# Driver.net
KiCad netlist of a schematic drawn in EAGLE
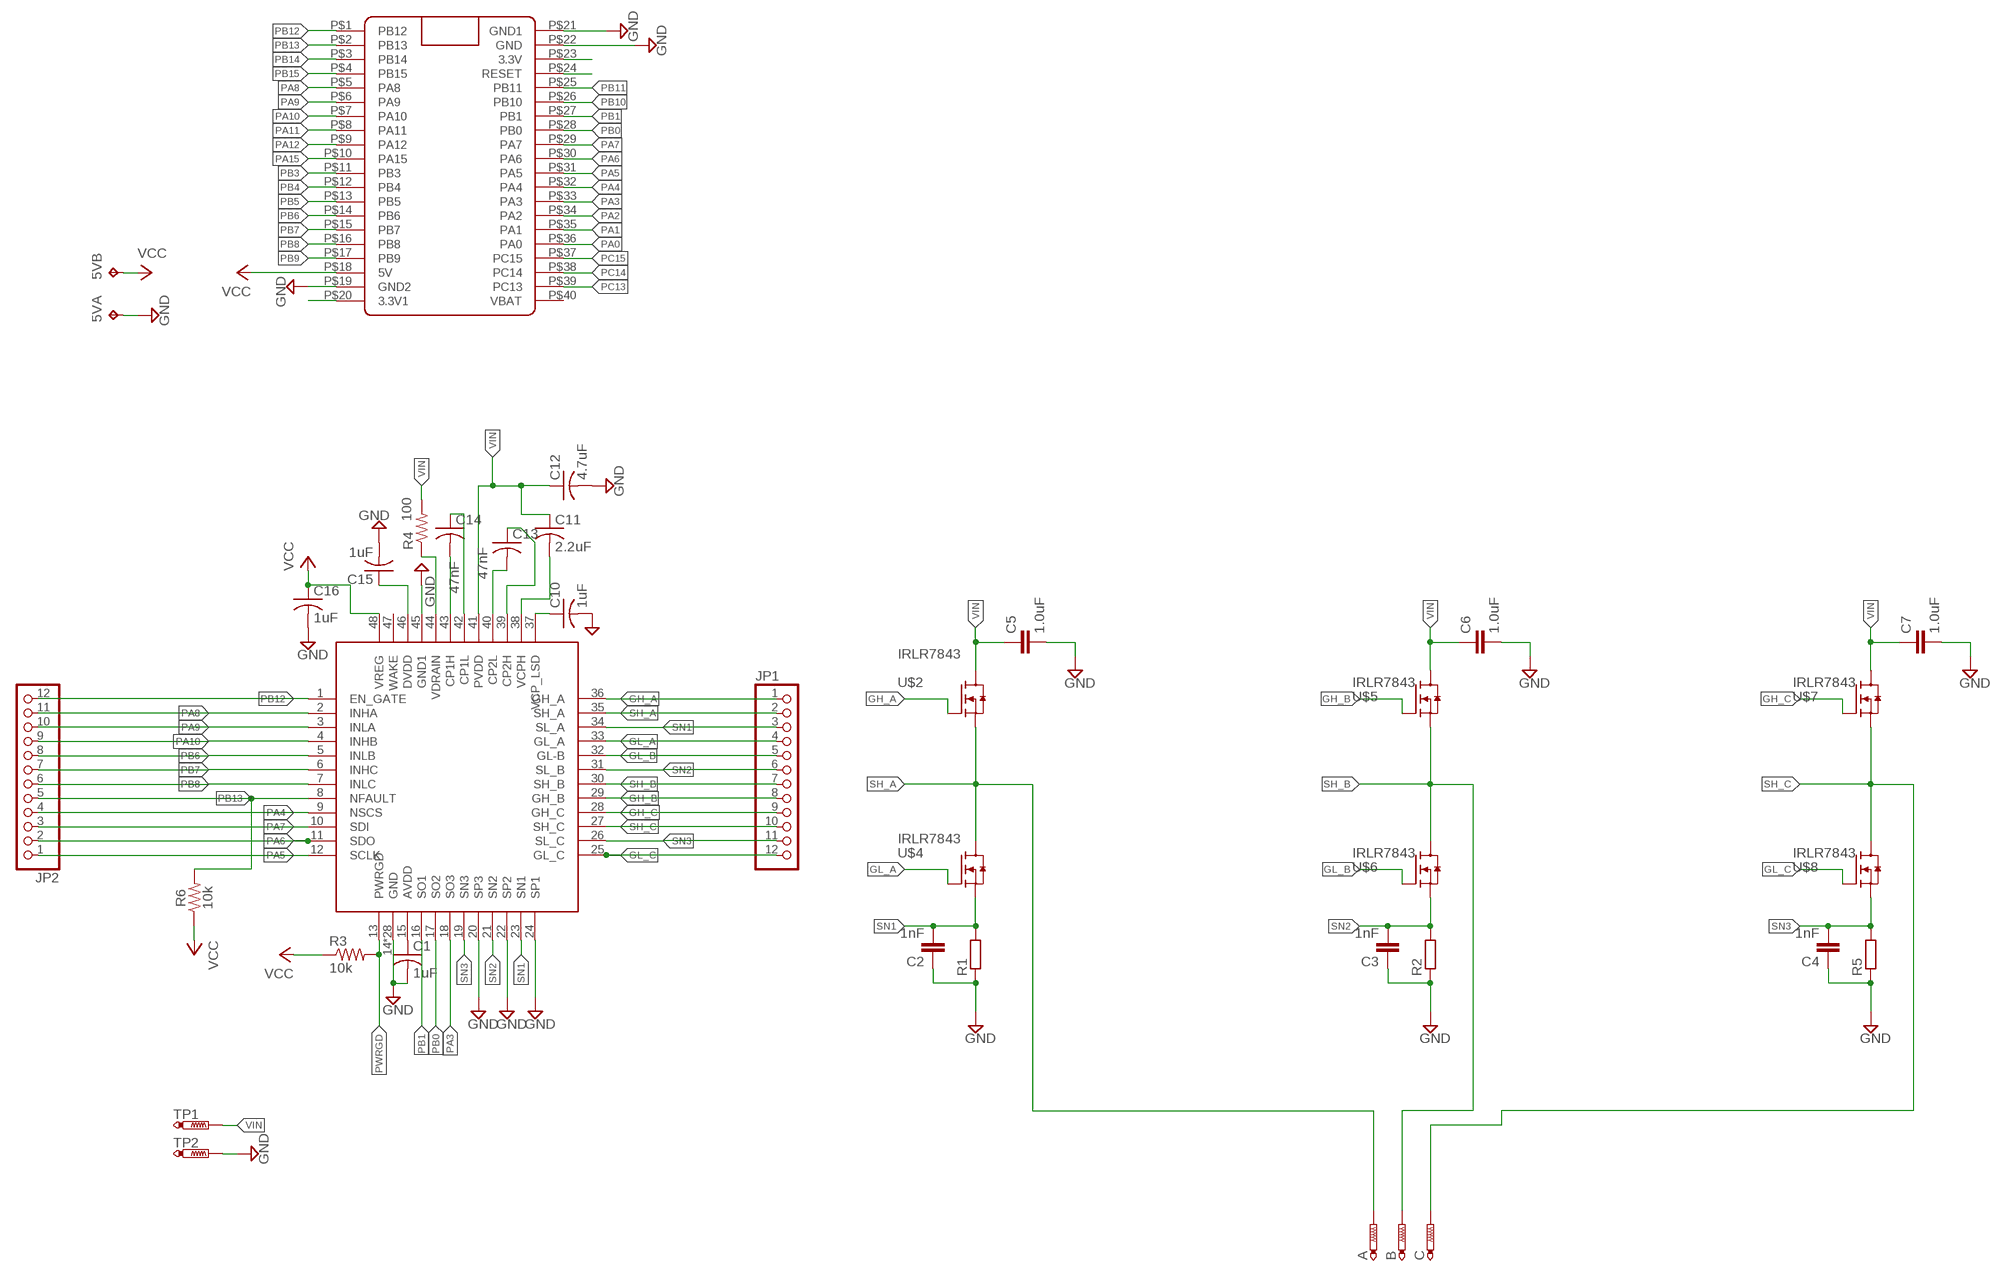
[diagram p0: schematic, sheet 1]

(export (version "E")
  (design (tool "Eeschema 10.0.6"))
  (components
    (comp (ref "5V")
      (value "TP2P2-38-17")
      (footprint "eagle-import:P2-38-17")
      (libsource (lib "eagle-import") (part "TP2P2-38-17"))
    )
    (comp (ref "A")
      (value "PTR1PAD1-20Y")
      (footprint "eagle-import:P1-20Y")
      (libsource (lib "eagle-import") (part "PTR1PAD1-20Y"))
    )
    (comp (ref "B")
      (value "PTR1PAD1-20Y")
      (footprint "eagle-import:P1-20Y")
      (libsource (lib "eagle-import") (part "PTR1PAD1-20Y"))
    )
    (comp (ref "C")
      (value "PTR1PAD1-20Y")
      (footprint "eagle-import:P1-20Y")
      (libsource (lib "eagle-import") (part "PTR1PAD1-20Y"))
    )
    (comp (ref "C1")
      (value "1uF")
      (footprint "eagle-import:C0603")
      (libsource (lib "eagle-import") (part "C-USC0603"))
    )
    (comp (ref "C2")
      (value "1nF")
      (footprint "eagle-import:0603")
      (libsource (lib "eagle-import") (part "1.0NF/1000PF-0603-50V-10%"))
    )
    (comp (ref "C3")
      (value "1nF")
      (footprint "eagle-import:0603")
      (libsource (lib "eagle-import") (part "1.0NF/1000PF-0603-50V-10%"))
    )
    (comp (ref "C4")
      (value "1nF")
      (footprint "eagle-import:0603")
      (libsource (lib "eagle-import") (part "1.0NF/1000PF-0603-50V-10%"))
    )
    (comp (ref "C5")
      (value "1.0uF")
      (footprint "eagle-import:0603")
      (libsource (lib "eagle-import") (part "1.0UF-0603-16V-10%-X7R"))
    )
    (comp (ref "C6")
      (value "1.0uF")
      (footprint "eagle-import:0603")
      (libsource (lib "eagle-import") (part "1.0UF-0603-16V-10%-X7R"))
    )
    (comp (ref "C7")
      (value "1.0uF")
      (footprint "eagle-import:0603")
      (libsource (lib "eagle-import") (part "1.0UF-0603-16V-10%-X7R"))
    )
    (comp (ref "C10")
      (value "1uF")
      (footprint "eagle-import:C0603")
      (libsource (lib "eagle-import") (part "C-USC0603"))
    )
    (comp (ref "C11")
      (value "2.2uF")
      (footprint "eagle-import:C0603")
      (libsource (lib "eagle-import") (part "C-USC0603"))
    )
    (comp (ref "C12")
      (value "4.7uF")
      (footprint "eagle-import:C0603")
      (libsource (lib "eagle-import") (part "C-USC0603"))
    )
    (comp (ref "C13")
      (value "47nF")
      (footprint "eagle-import:C0603")
      (libsource (lib "eagle-import") (part "C-USC0603"))
    )
    (comp (ref "C14")
      (value "47nF")
      (footprint "eagle-import:C0603")
      (libsource (lib "eagle-import") (part "C-USC0603"))
    )
    (comp (ref "C15")
      (value "1uF")
      (footprint "eagle-import:C0603")
      (libsource (lib "eagle-import") (part "C-USC0603"))
    )
    (comp (ref "C16")
      (value "1uF")
      (footprint "eagle-import:C0603")
      (libsource (lib "eagle-import") (part "C-USC0603"))
    )
    (comp (ref "JP1")
      (value "PINHD-1X12")
      (footprint "eagle-import:1X12")
      (libsource (lib "eagle-import") (part "PINHD-1X12"))
    )
    (comp (ref "JP2")
      (value "PINHD-1X12")
      (footprint "eagle-import:1X12")
      (libsource (lib "eagle-import") (part "PINHD-1X12"))
    )
    (comp (ref "R1")
      (value "R-EU_R2512")
      (footprint "eagle-import:R2512")
      (libsource (lib "eagle-import") (part "R-EU_R2512"))
    )
    (comp (ref "R2")
      (value "R-EU_R2512")
      (footprint "eagle-import:R2512")
      (libsource (lib "eagle-import") (part "R-EU_R2512"))
    )
    (comp (ref "R3")
      (value "10k")
      (footprint "eagle-import:R0603")
      (libsource (lib "eagle-import") (part "R-US_R0603"))
    )
    (comp (ref "R4")
      (value "100")
      (footprint "eagle-import:R0603")
      (libsource (lib "eagle-import") (part "R-US_R0603"))
    )
    (comp (ref "R5")
      (value "R-EU_R2512")
      (footprint "eagle-import:R2512")
      (libsource (lib "eagle-import") (part "R-EU_R2512"))
    )
    (comp (ref "R6")
      (value "10k")
      (footprint "eagle-import:0603")
      (libsource (lib "eagle-import") (part "10KOHM-0603-1/10W-1%"))
    )
    (comp (ref "TP1")
      (value "PTR1PAD1-20Y")
      (footprint "eagle-import:P1-20Y")
      (libsource (lib "eagle-import") (part "PTR1PAD1-20Y"))
    )
    (comp (ref "TP2")
      (value "PTR1PAD1-20Y")
      (footprint "eagle-import:P1-20Y")
      (libsource (lib "eagle-import") (part "PTR1PAD1-20Y"))
    )
    (comp (ref "U$1")
      (value "BLUE_PILLADVANCED")
      (footprint "eagle-import:BLUE_PILL_ADV")
      (libsource (lib "eagle-import") (part "BLUE_PILLADVANCED"))
    )
    (comp (ref "U$2")
      (value "IRLR7843")
      (footprint "eagle-import:TO252")
      (libsource (lib "eagle-import") (part "IRLR7843"))
    )
    (comp (ref "U$3")
      (value "DRV8305")
      (footprint "eagle-import:PFB_S-PQFP-G48")
      (libsource (lib "eagle-import") (part "DRV8305"))
    )
    (comp (ref "U$4")
      (value "IRLR7843")
      (footprint "eagle-import:TO252")
      (libsource (lib "eagle-import") (part "IRLR7843"))
    )
    (comp (ref "U$5")
      (value "IRLR7843")
      (footprint "eagle-import:TO252")
      (libsource (lib "eagle-import") (part "IRLR7843"))
    )
    (comp (ref "U$6")
      (value "IRLR7843")
      (footprint "eagle-import:TO252")
      (libsource (lib "eagle-import") (part "IRLR7843"))
    )
    (comp (ref "U$7")
      (value "IRLR7843")
      (footprint "eagle-import:TO252")
      (libsource (lib "eagle-import") (part "IRLR7843"))
    )
    (comp (ref "U$8")
      (value "IRLR7843")
      (footprint "eagle-import:TO252")
      (libsource (lib "eagle-import") (part "IRLR7843"))
    )
  )
  (nets
    (net (code "1") (name "GH_A") (class "Default")
      (node (ref "JP1") (pin "1") (pinfunction "1_1") (pintype "passive"))
      (node (ref "U$2") (pin "1") (pinfunction "G_1") (pintype "passive"))
      (node (ref "U$3") (pin "36") (pinfunction "GH_A_36") (pintype "bidirectional"))
    )
    (net (code "2") (name "GH_B") (class "Default")
      (node (ref "JP1") (pin "8") (pinfunction "8_8") (pintype "passive"))
      (node (ref "U$3") (pin "29") (pinfunction "GH_B_29") (pintype "bidirectional"))
      (node (ref "U$5") (pin "1") (pinfunction "G_1") (pintype "passive"))
    )
    (net (code "3") (name "GH_C") (class "Default")
      (node (ref "JP1") (pin "9") (pinfunction "9_9") (pintype "passive"))
      (node (ref "U$3") (pin "28") (pinfunction "GH_C_28") (pintype "bidirectional"))
      (node (ref "U$7") (pin "1") (pinfunction "G_1") (pintype "passive"))
    )
    (net (code "4") (name "GL_A") (class "Default")
      (node (ref "JP1") (pin "4") (pinfunction "4_4") (pintype "passive"))
      (node (ref "U$3") (pin "33") (pinfunction "GL_A_33") (pintype "bidirectional"))
      (node (ref "U$4") (pin "1") (pinfunction "G_1") (pintype "passive"))
    )
    (net (code "5") (name "GL_B") (class "Default")
      (node (ref "JP1") (pin "5") (pinfunction "5_5") (pintype "passive"))
      (node (ref "U$3") (pin "32") (pinfunction "GL-B_32") (pintype "bidirectional"))
      (node (ref "U$6") (pin "1") (pinfunction "G_1") (pintype "passive"))
    )
    (net (code "6") (name "GL_C") (class "Default")
      (node (ref "JP1") (pin "12") (pinfunction "12_12") (pintype "passive"))
      (node (ref "U$3") (pin "25") (pinfunction "GL_C_25") (pintype "bidirectional"))
      (node (ref "U$8") (pin "1") (pinfunction "G_1") (pintype "passive"))
    )
    (net (code "7") (name "GND") (class "Default")
      (node (ref "5V") (pin "TP-1") (pinfunction "TP_TP-1") (pintype "input"))
      (node (ref "C1") (pin "2") (pinfunction "2_2") (pintype "passive"))
      (node (ref "C10") (pin "2") (pinfunction "2_2") (pintype "passive"))
      (node (ref "C12") (pin "2") (pinfunction "2_2") (pintype "passive"))
      (node (ref "C15") (pin "2") (pinfunction "2_2") (pintype "passive"))
      (node (ref "C16") (pin "2") (pinfunction "2_2") (pintype "passive"))
      (node (ref "C2") (pin "1") (pinfunction "1_1") (pintype "passive"))
      (node (ref "C3") (pin "1") (pinfunction "1_1") (pintype "passive"))
      (node (ref "C4") (pin "1") (pinfunction "1_1") (pintype "passive"))
      (node (ref "C5") (pin "2") (pinfunction "2_2") (pintype "passive"))
      (node (ref "C6") (pin "2") (pinfunction "2_2") (pintype "passive"))
      (node (ref "C7") (pin "2") (pinfunction "2_2") (pintype "passive"))
      (node (ref "R1") (pin "1") (pinfunction "1_1") (pintype "passive"))
      (node (ref "R2") (pin "1") (pinfunction "1_1") (pintype "passive"))
      (node (ref "R5") (pin "1") (pinfunction "1_1") (pintype "passive"))
      (node (ref "TP2") (pin "TP") (pinfunction "TP_TP") (pintype "input"))
      (node (ref "U$1") (pin "P$19") (pinfunction "GND2_P$19") (pintype "bidirectional"))
      (node (ref "U$1") (pin "P$21") (pinfunction "GND1_P$21") (pintype "power_in"))
      (node (ref "U$1") (pin "P$22") (pinfunction "GND_P$22") (pintype "bidirectional"))
      (node (ref "U$3") (pin "14") (pinfunction "GND_14") (pintype "bidirectional"))
      (node (ref "U$3") (pin "20") (pinfunction "SP3_20") (pintype "bidirectional"))
      (node (ref "U$3") (pin "22") (pinfunction "SP2_22") (pintype "bidirectional"))
      (node (ref "U$3") (pin "24") (pinfunction "SP1_24") (pintype "bidirectional"))
      (node (ref "U$3") (pin "45") (pinfunction "GND1_45") (pintype "bidirectional"))
      (node (ref "U$3") (pin "P$1") (pinfunction "GND_P$1") (pintype "bidirectional"))
      (node (ref "U$3") (pin "P$10") (pinfunction "GND_P$10") (pintype "bidirectional"))
      (node (ref "U$3") (pin "P$11") (pinfunction "GND_P$11") (pintype "bidirectional"))
      (node (ref "U$3") (pin "P$12") (pinfunction "GND_P$12") (pintype "bidirectional"))
      (node (ref "U$3") (pin "P$13") (pinfunction "GND_P$13") (pintype "bidirectional"))
      (node (ref "U$3") (pin "P$14") (pinfunction "GND_P$14") (pintype "bidirectional"))
      (node (ref "U$3") (pin "P$15") (pinfunction "GND_P$15") (pintype "bidirectional"))
      (node (ref "U$3") (pin "P$16") (pinfunction "GND_P$16") (pintype "bidirectional"))
      (node (ref "U$3") (pin "P$17") (pinfunction "GND_P$17") (pintype "bidirectional"))
      (node (ref "U$3") (pin "P$18") (pinfunction "GND_P$18") (pintype "bidirectional"))
      (node (ref "U$3") (pin "P$19") (pinfunction "GND_P$19") (pintype "bidirectional"))
      (node (ref "U$3") (pin "P$2") (pinfunction "GND_P$2") (pintype "bidirectional"))
      (node (ref "U$3") (pin "P$20") (pinfunction "GND_P$20") (pintype "bidirectional"))
      (node (ref "U$3") (pin "P$21") (pinfunction "GND_P$21") (pintype "bidirectional"))
      (node (ref "U$3") (pin "P$22") (pinfunction "GND_P$22") (pintype "bidirectional"))
      (node (ref "U$3") (pin "P$23") (pinfunction "GND_P$23") (pintype "bidirectional"))
      (node (ref "U$3") (pin "P$24") (pinfunction "GND_P$24") (pintype "bidirectional"))
      (node (ref "U$3") (pin "P$25") (pinfunction "GND_P$25") (pintype "bidirectional"))
      (node (ref "U$3") (pin "P$26") (pinfunction "GND_P$26") (pintype "bidirectional"))
      (node (ref "U$3") (pin "P$27") (pinfunction "GND_P$27") (pintype "bidirectional"))
      (node (ref "U$3") (pin "P$3") (pinfunction "GND_P$3") (pintype "bidirectional"))
      (node (ref "U$3") (pin "P$4") (pinfunction "GND_P$4") (pintype "bidirectional"))
      (node (ref "U$3") (pin "P$5") (pinfunction "GND_P$5") (pintype "bidirectional"))
      (node (ref "U$3") (pin "P$6") (pinfunction "GND_P$6") (pintype "bidirectional"))
      (node (ref "U$3") (pin "P$7") (pinfunction "GND_P$7") (pintype "bidirectional"))
      (node (ref "U$3") (pin "P$8") (pinfunction "GND_P$8") (pintype "bidirectional"))
      (node (ref "U$3") (pin "P$9") (pinfunction "GND_P$9") (pintype "bidirectional"))
    )
    (net (code "8") (name "Net-(U$3-AVDD)") (class "Default")
      (node (ref "C1") (pin "1") (pinfunction "1_1") (pintype "passive"))
      (node (ref "U$3") (pin "15") (pinfunction "AVDD_15") (pintype "bidirectional"))
    )
    (net (code "9") (name "Net-(U$3-CP1H)") (class "Default")
      (node (ref "C14") (pin "2") (pinfunction "2_2") (pintype "passive"))
      (node (ref "U$3") (pin "43") (pinfunction "CP1H_43") (pintype "bidirectional"))
    )
    (net (code "10") (name "Net-(U$3-CP1L)") (class "Default")
      (node (ref "C14") (pin "1") (pinfunction "1_1") (pintype "passive"))
      (node (ref "U$3") (pin "42") (pinfunction "CP1L_42") (pintype "bidirectional"))
    )
    (net (code "11") (name "Net-(U$3-CP2H)") (class "Default")
      (node (ref "C13") (pin "1") (pinfunction "1_1") (pintype "passive"))
      (node (ref "U$3") (pin "39") (pinfunction "CP2H_39") (pintype "bidirectional"))
    )
    (net (code "12") (name "Net-(U$3-CP2L)") (class "Default")
      (node (ref "C13") (pin "2") (pinfunction "2_2") (pintype "passive"))
      (node (ref "U$3") (pin "40") (pinfunction "CP2L_40") (pintype "bidirectional"))
    )
    (net (code "13") (name "Net-(U$3-DVDD)") (class "Default")
      (node (ref "C15") (pin "1") (pinfunction "1_1") (pintype "passive"))
      (node (ref "U$3") (pin "46") (pinfunction "DVDD_46") (pintype "bidirectional"))
    )
    (net (code "14") (name "Net-(U$3-VCPH)") (class "Default")
      (node (ref "C11") (pin "2") (pinfunction "2_2") (pintype "passive"))
      (node (ref "U$3") (pin "38") (pinfunction "VCPH_38") (pintype "bidirectional"))
    )
    (net (code "15") (name "Net-(U$3-VCP_LSD)") (class "Default")
      (node (ref "C10") (pin "1") (pinfunction "1_1") (pintype "passive"))
      (node (ref "U$3") (pin "37") (pinfunction "VCP_LSD_37") (pintype "bidirectional"))
    )
    (net (code "16") (name "Net-(U$3-VDRAIN)") (class "Default")
      (node (ref "R4") (pin "1") (pinfunction "1_1") (pintype "passive"))
      (node (ref "U$3") (pin "44") (pinfunction "VDRAIN_44") (pintype "bidirectional"))
    )
    (net (code "17") (name "PA0") (class "Default")
      (node (ref "U$1") (pin "P$36") (pinfunction "PA0_P$36") (pintype "bidirectional"))
    )
    (net (code "18") (name "PA1") (class "Default")
      (node (ref "U$1") (pin "P$35") (pinfunction "PA1_P$35") (pintype "bidirectional"))
    )
    (net (code "19") (name "PA2") (class "Default")
      (node (ref "U$1") (pin "P$34") (pinfunction "PA2_P$34") (pintype "bidirectional"))
    )
    (net (code "20") (name "PA3") (class "Default")
      (node (ref "U$1") (pin "P$33") (pinfunction "PA3_P$33") (pintype "bidirectional"))
      (node (ref "U$3") (pin "18") (pinfunction "SO3_18") (pintype "bidirectional"))
    )
    (net (code "21") (name "PA4") (class "Default")
      (node (ref "JP2") (pin "4") (pinfunction "4_4") (pintype "passive"))
      (node (ref "U$1") (pin "P$32") (pinfunction "PA4_P$32") (pintype "bidirectional"))
      (node (ref "U$3") (pin "9") (pinfunction "NSCS_9") (pintype "bidirectional"))
    )
    (net (code "22") (name "PA5") (class "Default")
      (node (ref "JP2") (pin "1") (pinfunction "1_1") (pintype "passive"))
      (node (ref "U$1") (pin "P$31") (pinfunction "PA5_P$31") (pintype "bidirectional"))
      (node (ref "U$3") (pin "12") (pinfunction "SCLK_12") (pintype "bidirectional"))
    )
    (net (code "23") (name "PA6") (class "Default")
      (node (ref "JP2") (pin "2") (pinfunction "2_2") (pintype "passive"))
      (node (ref "U$1") (pin "P$30") (pinfunction "PA6_P$30") (pintype "bidirectional"))
      (node (ref "U$3") (pin "11") (pinfunction "SDO_11") (pintype "bidirectional"))
    )
    (net (code "24") (name "PA7") (class "Default")
      (node (ref "JP2") (pin "3") (pinfunction "3_3") (pintype "passive"))
      (node (ref "U$1") (pin "P$29") (pinfunction "PA7_P$29") (pintype "bidirectional"))
      (node (ref "U$3") (pin "10") (pinfunction "SDI_10") (pintype "bidirectional"))
    )
    (net (code "25") (name "PA8") (class "Default")
      (node (ref "JP2") (pin "11") (pinfunction "11_11") (pintype "passive"))
      (node (ref "U$1") (pin "P$5") (pinfunction "PA8_P$5") (pintype "bidirectional"))
      (node (ref "U$3") (pin "2") (pinfunction "INHA_2") (pintype "bidirectional"))
    )
    (net (code "26") (name "PA9") (class "Default")
      (node (ref "JP2") (pin "10") (pinfunction "10_10") (pintype "passive"))
      (node (ref "U$1") (pin "P$6") (pinfunction "PA9_P$6") (pintype "bidirectional"))
      (node (ref "U$3") (pin "3") (pinfunction "INLA_3") (pintype "bidirectional"))
    )
    (net (code "27") (name "PA10") (class "Default")
      (node (ref "JP2") (pin "9") (pinfunction "9_9") (pintype "passive"))
      (node (ref "U$1") (pin "P$7") (pinfunction "PA10_P$7") (pintype "bidirectional"))
      (node (ref "U$3") (pin "4") (pinfunction "INHB_4") (pintype "bidirectional"))
    )
    (net (code "28") (name "PA11") (class "Default")
      (node (ref "U$1") (pin "P$8") (pinfunction "PA11_P$8") (pintype "bidirectional"))
    )
    (net (code "29") (name "PA12") (class "Default")
      (node (ref "U$1") (pin "P$9") (pinfunction "PA12_P$9") (pintype "bidirectional"))
    )
    (net (code "30") (name "PA15") (class "Default")
      (node (ref "U$1") (pin "P$10") (pinfunction "PA15_P$10") (pintype "bidirectional"))
    )
    (net (code "31") (name "PB0") (class "Default")
      (node (ref "U$1") (pin "P$28") (pinfunction "PB0_P$28") (pintype "bidirectional"))
      (node (ref "U$3") (pin "17") (pinfunction "SO2_17") (pintype "bidirectional"))
    )
    (net (code "32") (name "PB1") (class "Default")
      (node (ref "U$1") (pin "P$27") (pinfunction "PB1_P$27") (pintype "bidirectional"))
      (node (ref "U$3") (pin "16") (pinfunction "SO1_16") (pintype "bidirectional"))
    )
    (net (code "33") (name "PB3") (class "Default")
      (node (ref "U$1") (pin "P$11") (pinfunction "PB3_P$11") (pintype "bidirectional"))
    )
    (net (code "34") (name "PB4") (class "Default")
      (node (ref "U$1") (pin "P$12") (pinfunction "PB4_P$12") (pintype "bidirectional"))
    )
    (net (code "35") (name "PB5") (class "Default")
      (node (ref "U$1") (pin "P$13") (pinfunction "PB5_P$13") (pintype "bidirectional"))
    )
    (net (code "36") (name "PB6") (class "Default")
      (node (ref "JP2") (pin "8") (pinfunction "8_8") (pintype "passive"))
      (node (ref "U$1") (pin "P$14") (pinfunction "PB6_P$14") (pintype "bidirectional"))
      (node (ref "U$3") (pin "5") (pinfunction "INLB_5") (pintype "bidirectional"))
    )
    (net (code "37") (name "PB7") (class "Default")
      (node (ref "JP2") (pin "7") (pinfunction "7_7") (pintype "passive"))
      (node (ref "U$1") (pin "P$15") (pinfunction "PB7_P$15") (pintype "bidirectional"))
      (node (ref "U$3") (pin "6") (pinfunction "INHC_6") (pintype "bidirectional"))
    )
    (net (code "38") (name "PB8") (class "Default")
      (node (ref "JP2") (pin "6") (pinfunction "6_6") (pintype "passive"))
      (node (ref "U$1") (pin "P$16") (pinfunction "PB8_P$16") (pintype "bidirectional"))
      (node (ref "U$3") (pin "7") (pinfunction "INLC_7") (pintype "bidirectional"))
    )
    (net (code "39") (name "PB9") (class "Default")
      (node (ref "U$1") (pin "P$17") (pinfunction "PB9_P$17") (pintype "bidirectional"))
    )
    (net (code "40") (name "PB10") (class "Default")
      (node (ref "U$1") (pin "P$26") (pinfunction "PB10_P$26") (pintype "bidirectional"))
    )
    (net (code "41") (name "PB11") (class "Default")
      (node (ref "U$1") (pin "P$25") (pinfunction "PB11_P$25") (pintype "bidirectional"))
    )
    (net (code "42") (name "PB12") (class "Default")
      (node (ref "JP2") (pin "12") (pinfunction "12_12") (pintype "passive"))
      (node (ref "U$1") (pin "P$1") (pinfunction "PB12_P$1") (pintype "bidirectional"))
      (node (ref "U$3") (pin "1") (pinfunction "EN_GATE_1") (pintype "bidirectional"))
    )
    (net (code "43") (name "PB13") (class "Default")
      (node (ref "JP2") (pin "5") (pinfunction "5_5") (pintype "passive"))
      (node (ref "R6") (pin "2") (pinfunction "2_2") (pintype "passive"))
      (node (ref "U$1") (pin "P$2") (pinfunction "PB13_P$2") (pintype "bidirectional"))
      (node (ref "U$3") (pin "8") (pinfunction "NFAULT_8") (pintype "bidirectional"))
    )
    (net (code "44") (name "PB14") (class "Default")
      (node (ref "U$1") (pin "P$3") (pinfunction "PB14_P$3") (pintype "bidirectional"))
    )
    (net (code "45") (name "PB15") (class "Default")
      (node (ref "U$1") (pin "P$4") (pinfunction "PB15_P$4") (pintype "bidirectional"))
    )
    (net (code "46") (name "PC13") (class "Default")
      (node (ref "U$1") (pin "P$39") (pinfunction "PC13_P$39") (pintype "bidirectional"))
    )
    (net (code "47") (name "PC14") (class "Default")
      (node (ref "U$1") (pin "P$38") (pinfunction "PC14_P$38") (pintype "bidirectional"))
    )
    (net (code "48") (name "PC15") (class "Default")
      (node (ref "U$1") (pin "P$37") (pinfunction "PC15_P$37") (pintype "bidirectional"))
    )
    (net (code "49") (name "PWRGD") (class "Default")
      (node (ref "R3") (pin "2") (pinfunction "2_2") (pintype "passive"))
      (node (ref "U$3") (pin "13") (pinfunction "PWRGD_13") (pintype "bidirectional"))
    )
    (net (code "50") (name "SH_A") (class "Default")
      (node (ref "A") (pin "TP") (pinfunction "TP_TP") (pintype "input"))
      (node (ref "JP1") (pin "2") (pinfunction "2_2") (pintype "passive"))
      (node (ref "U$2") (pin "2") (pinfunction "S_2") (pintype "passive"))
      (node (ref "U$3") (pin "35") (pinfunction "SH_A_35") (pintype "bidirectional"))
      (node (ref "U$4") (pin "3") (pinfunction "D_3") (pintype "passive"))
    )
    (net (code "51") (name "SH_B") (class "Default")
      (node (ref "B") (pin "TP") (pinfunction "TP_TP") (pintype "input"))
      (node (ref "JP1") (pin "7") (pinfunction "7_7") (pintype "passive"))
      (node (ref "U$3") (pin "30") (pinfunction "SH_B_30") (pintype "bidirectional"))
      (node (ref "U$5") (pin "2") (pinfunction "S_2") (pintype "passive"))
      (node (ref "U$6") (pin "3") (pinfunction "D_3") (pintype "passive"))
    )
    (net (code "52") (name "SH_C") (class "Default")
      (node (ref "C") (pin "TP") (pinfunction "TP_TP") (pintype "input"))
      (node (ref "JP1") (pin "10") (pinfunction "10_10") (pintype "passive"))
      (node (ref "U$3") (pin "27") (pinfunction "SH_C_27") (pintype "bidirectional"))
      (node (ref "U$7") (pin "2") (pinfunction "S_2") (pintype "passive"))
      (node (ref "U$8") (pin "3") (pinfunction "D_3") (pintype "passive"))
    )
    (net (code "53") (name "SN1") (class "Default")
      (node (ref "C2") (pin "2") (pinfunction "2_2") (pintype "passive"))
      (node (ref "JP1") (pin "3") (pinfunction "3_3") (pintype "passive"))
      (node (ref "R1") (pin "2") (pinfunction "2_2") (pintype "passive"))
      (node (ref "U$3") (pin "23") (pinfunction "SN1_23") (pintype "bidirectional"))
      (node (ref "U$3") (pin "34") (pinfunction "SL_A_34") (pintype "bidirectional"))
      (node (ref "U$4") (pin "2") (pinfunction "S_2") (pintype "passive"))
    )
    (net (code "54") (name "SN2") (class "Default")
      (node (ref "C3") (pin "2") (pinfunction "2_2") (pintype "passive"))
      (node (ref "JP1") (pin "6") (pinfunction "6_6") (pintype "passive"))
      (node (ref "R2") (pin "2") (pinfunction "2_2") (pintype "passive"))
      (node (ref "U$3") (pin "21") (pinfunction "SN2_21") (pintype "bidirectional"))
      (node (ref "U$3") (pin "31") (pinfunction "SL_B_31") (pintype "bidirectional"))
      (node (ref "U$6") (pin "2") (pinfunction "S_2") (pintype "passive"))
    )
    (net (code "55") (name "SN3") (class "Default")
      (node (ref "C4") (pin "2") (pinfunction "2_2") (pintype "passive"))
      (node (ref "JP1") (pin "11") (pinfunction "11_11") (pintype "passive"))
      (node (ref "R5") (pin "2") (pinfunction "2_2") (pintype "passive"))
      (node (ref "U$3") (pin "19") (pinfunction "SN3_19") (pintype "bidirectional"))
      (node (ref "U$3") (pin "26") (pinfunction "SL_C_26") (pintype "bidirectional"))
      (node (ref "U$8") (pin "2") (pinfunction "S_2") (pintype "passive"))
    )
    (net (code "56") (name "VCC") (class "Default")
      (node (ref "5V") (pin "TP-2") (pinfunction "TP_TP-2") (pintype "input"))
      (node (ref "C16") (pin "1") (pinfunction "1_1") (pintype "passive"))
      (node (ref "R3") (pin "1") (pinfunction "1_1") (pintype "passive"))
      (node (ref "R6") (pin "1") (pinfunction "1_1") (pintype "passive"))
      (node (ref "U$1") (pin "P$18") (pinfunction "5V_P$18") (pintype "bidirectional"))
      (node (ref "U$3") (pin "48") (pinfunction "VREG_48") (pintype "bidirectional"))
    )
    (net (code "57") (name "VIN") (class "Default")
      (node (ref "C11") (pin "1") (pinfunction "1_1") (pintype "passive"))
      (node (ref "C12") (pin "1") (pinfunction "1_1") (pintype "passive"))
      (node (ref "C5") (pin "1") (pinfunction "1_1") (pintype "passive"))
      (node (ref "C6") (pin "1") (pinfunction "1_1") (pintype "passive"))
      (node (ref "C7") (pin "1") (pinfunction "1_1") (pintype "passive"))
      (node (ref "R4") (pin "2") (pinfunction "2_2") (pintype "passive"))
      (node (ref "TP1") (pin "TP") (pinfunction "TP_TP") (pintype "input"))
      (node (ref "U$2") (pin "3") (pinfunction "D_3") (pintype "passive"))
      (node (ref "U$3") (pin "41") (pinfunction "PVDD_41") (pintype "bidirectional"))
      (node (ref "U$5") (pin "3") (pinfunction "D_3") (pintype "passive"))
      (node (ref "U$7") (pin "3") (pinfunction "D_3") (pintype "passive"))
    )
    (net (code "58") (name "unconnected-(U$1-3.3V-PadP$23)") (class "Default")
      (node (ref "U$1") (pin "P$23") (pinfunction "3.3V_P$23") (pintype "bidirectional"))
    )
    (net (code "59") (name "unconnected-(U$1-3.3V1-PadP$20)") (class "Default")
      (node (ref "U$1") (pin "P$20") (pinfunction "3.3V1_P$20") (pintype "bidirectional"))
    )
    (net (code "60") (name "unconnected-(U$1-RESET-PadP$24)") (class "Default")
      (node (ref "U$1") (pin "P$24") (pinfunction "RESET_P$24") (pintype "bidirectional"))
    )
    (net (code "61") (name "unconnected-(U$1-VBAT-PadP$40)") (class "Default")
      (node (ref "U$1") (pin "P$40") (pinfunction "VBAT_P$40") (pintype "bidirectional"))
    )
    (net (code "62") (name "unconnected-(U$3-WAKE-Pad47)") (class "Default")
      (node (ref "U$3") (pin "47") (pinfunction "WAKE_47") (pintype "bidirectional"))
    )
  )
)
